# Audio_Output_XLR1.net
KiCad netlist of a schematic drawn in Altium Designer
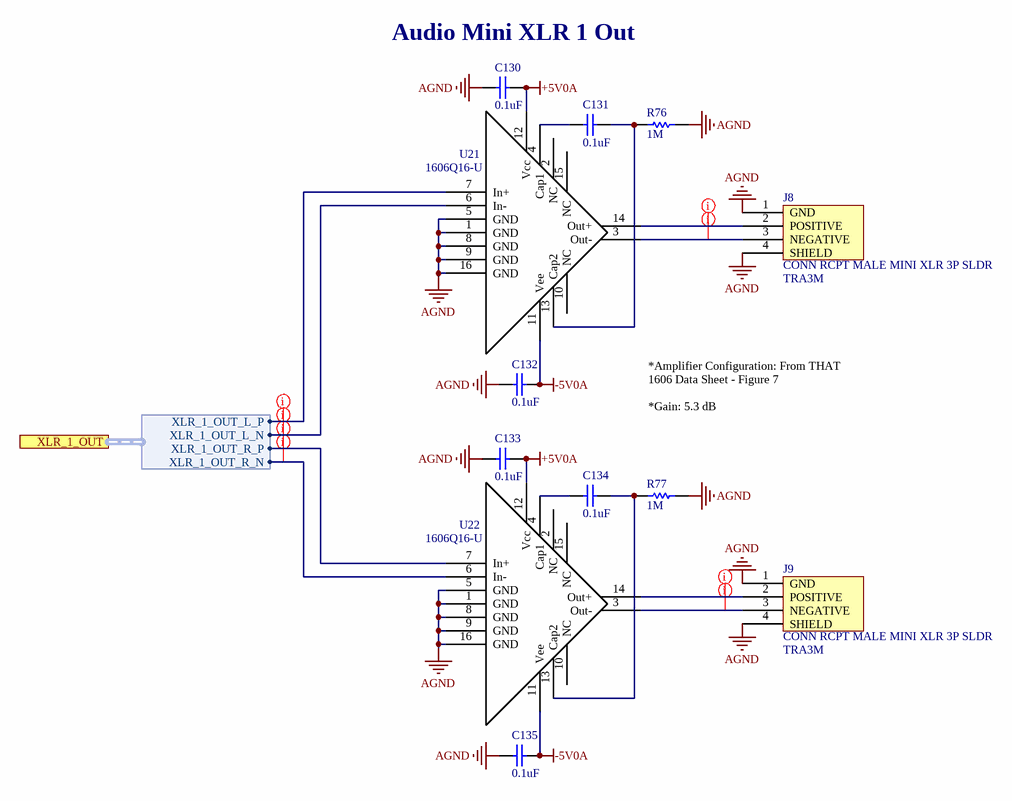
[diagram p0: Audio_Output_XLR1.SchDoc]

(export (version "E")
  (design (tool "Eeschema 10.0.6"))
  (components
    (comp (ref "C130")
      (value "CL10F104ZO8NNNC")
      (footprint "3-0603_L")
      (description "CAP CER 0.1UF 16V Y5V 0603")
      (fields
        (field (name "MANUFACTURER") "Samsung")
        (field (name "TOLERANCE") "80%")
        (field (name "CAPACITANCE") "0.1uF")
      )
      (libsource (lib "Schematic_Components_CD") (part "CL10F104ZO8NNNC"))
    )
    (comp (ref "C131")
      (value "CL10F104ZO8NNNC")
      (footprint "3-0603_L")
      (description "CAP CER 0.1UF 16V Y5V 0603")
      (fields
        (field (name "MANUFACTURER") "Samsung")
        (field (name "TOLERANCE") "80%")
        (field (name "CAPACITANCE") "0.1uF")
      )
      (libsource (lib "Schematic_Components_CD") (part "CL10F104ZO8NNNC"))
    )
    (comp (ref "C132")
      (value "CL10F104ZO8NNNC")
      (footprint "3-0603_L")
      (description "CAP CER 0.1UF 16V Y5V 0603")
      (fields
        (field (name "MANUFACTURER") "Samsung")
        (field (name "TOLERANCE") "80%")
        (field (name "CAPACITANCE") "0.1uF")
      )
      (libsource (lib "Schematic_Components_CD") (part "CL10F104ZO8NNNC"))
    )
    (comp (ref "C133")
      (value "CL10F104ZO8NNNC")
      (footprint "3-0603_L")
      (description "CAP CER 0.1UF 16V Y5V 0603")
      (fields
        (field (name "MANUFACTURER") "Samsung")
        (field (name "TOLERANCE") "80%")
        (field (name "CAPACITANCE") "0.1uF")
      )
      (libsource (lib "Schematic_Components_CD") (part "CL10F104ZO8NNNC"))
    )
    (comp (ref "C134")
      (value "CL10F104ZO8NNNC")
      (footprint "3-0603_L")
      (description "CAP CER 0.1UF 16V Y5V 0603")
      (fields
        (field (name "MANUFACTURER") "Samsung")
        (field (name "TOLERANCE") "80%")
        (field (name "CAPACITANCE") "0.1uF")
      )
      (libsource (lib "Schematic_Components_CD") (part "CL10F104ZO8NNNC"))
    )
    (comp (ref "C135")
      (value "CL10F104ZO8NNNC")
      (footprint "3-0603_L")
      (description "CAP CER 0.1UF 16V Y5V 0603")
      (fields
        (field (name "MANUFACTURER") "Samsung")
        (field (name "TOLERANCE") "80%")
        (field (name "CAPACITANCE") "0.1uF")
      )
      (libsource (lib "Schematic_Components_CD") (part "CL10F104ZO8NNNC"))
    )
    (comp (ref "J8")
      (value "CONN RCPT MALE MINI XLR 3P SLDR")
      (footprint "TRA3M")
      (description "3 Position Circular Connector Receptacle, Male Pins Solder Silver")
      (fields (field (name "MANUFACTURER") "Switchcraft") (field (name "MANUFACTURER PART NUMBER") "TRA3M"))
      (libsource (lib "Schematic_Components_CD") (part "TRA3M"))
    )
    (comp (ref "J9")
      (value "CONN RCPT MALE MINI XLR 3P SLDR")
      (footprint "TRA3M")
      (description "3 Position Circular Connector Receptacle, Male Pins Solder Silver")
      (fields (field (name "MANUFACTURER") "Switchcraft") (field (name "MANUFACTURER PART NUMBER") "TRA3M"))
      (libsource (lib "Schematic_Components_CD") (part "TRA3M"))
    )
    (comp (ref "R76")
      (value "RMCF0603FG1M00")
      (footprint "3-0603_R_L")
      (description "RES 1M OHM 1% 1/10W 0603")
      (fields
        (field (name "MANUFACTURER") "Stackpole Electronics")
        (field (name "TOLERANCE") "1%")
        (field (name "RESISTANCE") "1M")
      )
      (libsource (lib "Schematic_Components_CD") (part "RMCF0603FG1M00"))
    )
    (comp (ref "R77")
      (value "RMCF0603FG1M00")
      (footprint "3-0603_R_L")
      (description "RES 1M OHM 1% 1/10W 0603")
      (fields
        (field (name "MANUFACTURER") "Stackpole Electronics")
        (field (name "TOLERANCE") "1%")
        (field (name "RESISTANCE") "1M")
      )
      (libsource (lib "Schematic_Components_CD") (part "RMCF0603FG1M00"))
    )
    (comp (ref "U21")
      (value "1606Q16-U")
      (footprint "SOP64P600X175-16N")
      (description "Audio Amplifiers Balanced Audio Line Driver IC")
      (fields (field (name "MANUFACTURER") "THAT") (field (name "MANUFACTURER PART NUMBER") "1606Q16-U"))
      (libsource (lib "Schematic_Components_CD") (part "1606Q16-U"))
    )
    (comp (ref "U22")
      (value "1606Q16-U")
      (footprint "SOP64P600X175-16N")
      (description "Audio Amplifiers Balanced Audio Line Driver IC")
      (fields (field (name "MANUFACTURER") "THAT") (field (name "MANUFACTURER PART NUMBER") "1606Q16-U"))
      (libsource (lib "Schematic_Components_CD") (part "1606Q16-U"))
    )
  )
  (nets
    (net (code "2") (name "+5V0A") (class "Default")
      (node (ref "C130") (pin "1") (pinfunction "1_1") (pintype "passive"))
      (node (ref "C133") (pin "1") (pinfunction "1_1") (pintype "passive"))
      (node (ref "U21") (pin "12") (pinfunction "Vcc_12") (pintype "passive"))
      (node (ref "U22") (pin "12") (pinfunction "Vcc_12") (pintype "passive"))
    )
    (net (code "3") (name "-5V0A") (class "Default")
      (node (ref "C132") (pin "1") (pinfunction "1_1") (pintype "passive"))
      (node (ref "C135") (pin "1") (pinfunction "1_1") (pintype "passive"))
      (node (ref "U21") (pin "11") (pinfunction "Vee_11") (pintype "passive"))
      (node (ref "U22") (pin "11") (pinfunction "Vee_11") (pintype "passive"))
    )
    (net (code "4") (name "/XLR_1_OUT_L_N") (class "Default")
      (node (ref "U21") (pin "6") (pinfunction "In-_6") (pintype "passive"))
    )
    (net (code "5") (name "/XLR_1_OUT_L_P") (class "Default")
      (node (ref "U21") (pin "7") (pinfunction "In+_7") (pintype "passive"))
    )
    (net (code "6") (name "/XLR_1_OUT_R_N") (class "Default")
      (node (ref "U22") (pin "6") (pinfunction "In-_6") (pintype "passive"))
    )
    (net (code "7") (name "/XLR_1_OUT_R_P") (class "Default")
      (node (ref "U22") (pin "7") (pinfunction "In+_7") (pintype "passive"))
    )
    (net (code "9") (name "AGND") (class "Default")
      (node (ref "C130") (pin "2") (pinfunction "2_2") (pintype "passive"))
      (node (ref "C132") (pin "2") (pinfunction "2_2") (pintype "passive"))
      (node (ref "C133") (pin "2") (pinfunction "2_2") (pintype "passive"))
      (node (ref "C135") (pin "2") (pinfunction "2_2") (pintype "passive"))
      (node (ref "J8") (pin "1") (pinfunction "GND_1") (pintype "passive"))
      (node (ref "J8") (pin "4") (pinfunction "SHIELD_4") (pintype "passive"))
      (node (ref "J9") (pin "1") (pinfunction "GND_1") (pintype "passive"))
      (node (ref "J9") (pin "4") (pinfunction "SHIELD_4") (pintype "passive"))
      (node (ref "R76") (pin "2") (pinfunction "2_2") (pintype "passive"))
      (node (ref "R77") (pin "2") (pinfunction "2_2") (pintype "passive"))
      (node (ref "U21") (pin "1") (pinfunction "GND_1") (pintype "passive"))
      (node (ref "U21") (pin "16") (pinfunction "GND_16") (pintype "passive"))
      (node (ref "U21") (pin "5") (pinfunction "GND_5") (pintype "passive"))
      (node (ref "U21") (pin "8") (pinfunction "GND_8") (pintype "passive"))
      (node (ref "U21") (pin "9") (pinfunction "GND_9") (pintype "passive"))
      (node (ref "U22") (pin "1") (pinfunction "GND_1") (pintype "passive"))
      (node (ref "U22") (pin "16") (pinfunction "GND_16") (pintype "passive"))
      (node (ref "U22") (pin "5") (pinfunction "GND_5") (pintype "passive"))
      (node (ref "U22") (pin "8") (pinfunction "GND_8") (pintype "passive"))
      (node (ref "U22") (pin "9") (pinfunction "GND_9") (pintype "passive"))
    )
    (net (code "10") (name "Net-(J8-NEGATIVE)") (class "Default")
      (node (ref "J8") (pin "3") (pinfunction "NEGATIVE_3") (pintype "passive"))
      (node (ref "U21") (pin "3") (pinfunction "Out-_3") (pintype "passive"))
    )
    (net (code "11") (name "Net-(J8-POSITIVE)") (class "Default")
      (node (ref "J8") (pin "2") (pinfunction "POSITIVE_2") (pintype "passive"))
      (node (ref "U21") (pin "14") (pinfunction "Out+_14") (pintype "passive"))
    )
    (net (code "12") (name "Net-(J9-NEGATIVE)") (class "Default")
      (node (ref "J9") (pin "3") (pinfunction "NEGATIVE_3") (pintype "passive"))
      (node (ref "U22") (pin "3") (pinfunction "Out-_3") (pintype "passive"))
    )
    (net (code "13") (name "Net-(J9-POSITIVE)") (class "Default")
      (node (ref "J9") (pin "2") (pinfunction "POSITIVE_2") (pintype "passive"))
      (node (ref "U22") (pin "14") (pinfunction "Out+_14") (pintype "passive"))
    )
    (net (code "14") (name "Net-(U21-Cap1)") (class "Default")
      (node (ref "C131") (pin "2") (pinfunction "2_2") (pintype "passive"))
      (node (ref "U21") (pin "4") (pinfunction "Cap1_4") (pintype "passive"))
    )
    (net (code "15") (name "Net-(U21-Cap2)") (class "Default")
      (node (ref "C131") (pin "1") (pinfunction "1_1") (pintype "passive"))
      (node (ref "R76") (pin "1") (pinfunction "1_1") (pintype "passive"))
      (node (ref "U21") (pin "13") (pinfunction "Cap2_13") (pintype "passive"))
    )
    (net (code "16") (name "Net-(U22-Cap1)") (class "Default")
      (node (ref "C134") (pin "2") (pinfunction "2_2") (pintype "passive"))
      (node (ref "U22") (pin "4") (pinfunction "Cap1_4") (pintype "passive"))
    )
    (net (code "17") (name "Net-(U22-Cap2)") (class "Default")
      (node (ref "C134") (pin "1") (pinfunction "1_1") (pintype "passive"))
      (node (ref "R77") (pin "1") (pinfunction "1_1") (pintype "passive"))
      (node (ref "U22") (pin "13") (pinfunction "Cap2_13") (pintype "passive"))
    )
    (net (code "18") (name "unconnected-(U21-NC-Pad2)") (class "Default")
      (node (ref "U21") (pin "2") (pinfunction "NC_2") (pintype "passive"))
    )
    (net (code "19") (name "unconnected-(U21-NC-Pad10)") (class "Default")
      (node (ref "U21") (pin "10") (pinfunction "NC_10") (pintype "passive"))
    )
    (net (code "20") (name "unconnected-(U21-NC-Pad15)") (class "Default")
      (node (ref "U21") (pin "15") (pinfunction "NC_15") (pintype "passive"))
    )
    (net (code "21") (name "unconnected-(U22-NC-Pad2)") (class "Default")
      (node (ref "U22") (pin "2") (pinfunction "NC_2") (pintype "passive"))
    )
    (net (code "22") (name "unconnected-(U22-NC-Pad10)") (class "Default")
      (node (ref "U22") (pin "10") (pinfunction "NC_10") (pintype "passive"))
    )
    (net (code "23") (name "unconnected-(U22-NC-Pad15)") (class "Default")
      (node (ref "U22") (pin "15") (pinfunction "NC_15") (pintype "passive"))
    )
  )
)
